# 3DP-GLCD.net
KiCad netlist of a schematic drawn in Altium Designer
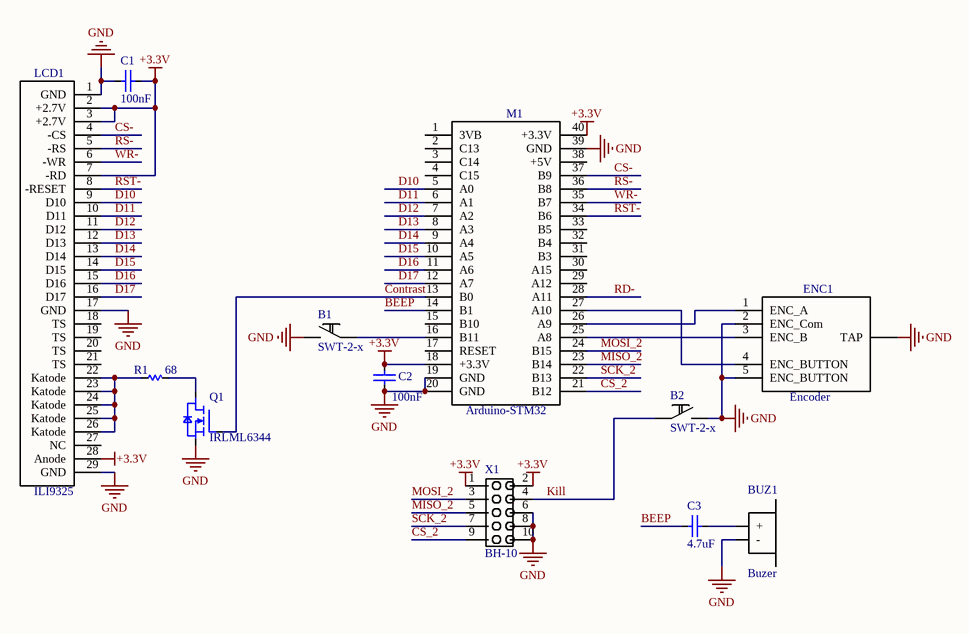
[diagram p0: 3DP-GLCD.SchDoc]

(export (version "E")
  (design (tool "Eeschema 10.0.6"))
  (components
    (comp (ref "B1") (value "SWT-2-x") (footprint "SWT-2-x") (libsource (lib "My_Schlib") (part "SWT-2-x")))
    (comp (ref "B2") (value "SWT-2-x") (footprint "SWT-2-x") (libsource (lib "My_Schlib") (part "SWT-2-x")))
    (comp (ref "BUZ1") (value "Buzer") (footprint "Buzer_12xx") (libsource (lib "My_Schlib") (part "Buzer")))
    (comp (ref "C1")
      (value "100nF")
      (footprint "C0805_Murata")
      (fields
        (field (name "PART NUMBER") "GRM21BR71H104KA01L")
        (field (name "VOLTAGE") "50V")
        (field (name "TOLERANCE") "10 %")
      )
      (libsource (lib "CorpLib") (part "Cap"))
    )
    (comp (ref "C2")
      (value "100nF")
      (footprint "C0805_Murata")
      (fields
        (field (name "PART NUMBER") "GRM21BR71H104KA01L")
        (field (name "VOLTAGE") "50V")
        (field (name "TOLERANCE") "10 %")
      )
      (libsource (lib "CorpLib") (part "Cap"))
    )
    (comp (ref "C3")
      (value "4.7uF")
      (footprint "C1206_Murata")
      (fields
        (field (name "PART NUMBER") "GRM31CR71H475KA12L")
        (field (name "VOLTAGE") "50V")
        (field (name "TOLERANCE") "10 %")
      )
      (libsource (lib "CorpLib") (part "Cap"))
    )
    (comp (ref "ENC1")
      (value "Encoder")
      (footprint "Encoder_bot")
      (description "Rotary Encoder with button")
      (libsource (lib "My_Schlib") (part "Encoder"))
    )
    (comp (ref "LCD1")
      (value "ILI9325")
      (footprint "LCD-ILI9325-29pin-top")
      (description "TFT LCD")
      (libsource (lib "My_Schlib") (part "LCD-ILI9325-29pin"))
    )
    (comp (ref "M1")
      (value "Arduino-STM32")
      (footprint "ARDUINO-STM32")
      (libsource (lib "My_Schlib") (part "ARDUINO-STM32"))
    )
    (comp (ref "Q1")
      (value "IRLML6344")
      (footprint "SOT23-3_IR")
      (description "30 V, 5.0 A, 0.029 Ohm Single N-Channel HEXFET Power MOSFET")
      (fields
        (field (name "PART NUMBER") "IRLML6344TRPBF")
        (field (name "PART LABEL") "IRLML6344")
        (field (name "MANUFACTURER") "International Rectifier")
      )
      (libsource (lib "CorpLib") (part "IRLML6344"))
    )
    (comp (ref "R1")
      (value "68")
      (footprint "R0805_UniOhm")
      (fields
        (field (name "PART NUMBER") "0805S8F4700T50")
        (field (name "TOLERANCE") "1 %")
        (field (name "MANUFACTURER") "uniOhm")
      )
      (libsource (lib "CorpLib") (part "R"))
    )
    (comp (ref "X1") (value "BH-10") (footprint "BH-10") (libsource (lib "My_Schlib") (part "BH-10_2")))
  )
  (nets
    (net (code "1") (name "+3.3V") (class "Default")
      (node (ref "C1") (pin "1") (pinfunction "1_1") (pintype "passive"))
      (node (ref "C2") (pin "1") (pinfunction "1_1") (pintype "passive"))
      (node (ref "LCD1") (pin "2") (pinfunction "+2.7V_2") (pintype "passive"))
      (node (ref "LCD1") (pin "28") (pinfunction "Anode_28") (pintype "passive"))
      (node (ref "LCD1") (pin "3") (pinfunction "+2.7V_3") (pintype "passive"))
      (node (ref "LCD1") (pin "7") (pinfunction "-RD_7") (pintype "passive"))
      (node (ref "M1") (pin "18") (pinfunction "+3.3V_18") (pintype "passive"))
      (node (ref "M1") (pin "40") (pinfunction "+3.3V_40") (pintype "passive"))
      (node (ref "X1") (pin "1") (pinfunction "1_1") (pintype "passive"))
      (node (ref "X1") (pin "2") (pinfunction "2_2") (pintype "passive"))
    )
    (net (code "2") (name "/BEEP") (class "Default")
      (node (ref "C3") (pin "1") (pinfunction "1_1") (pintype "passive"))
      (node (ref "M1") (pin "14") (pinfunction "B1_14") (pintype "passive"))
    )
    (net (code "3") (name "/CS-") (class "Default")
      (node (ref "LCD1") (pin "4") (pinfunction "-CS_4") (pintype "passive"))
      (node (ref "M1") (pin "37") (pinfunction "B9_37") (pintype "passive"))
    )
    (net (code "4") (name "/CS_2") (class "Default")
      (node (ref "M1") (pin "21") (pinfunction "B12_21") (pintype "passive"))
      (node (ref "X1") (pin "9") (pinfunction "9_9") (pintype "passive"))
    )
    (net (code "5") (name "/Contrast") (class "Default")
      (node (ref "M1") (pin "13") (pinfunction "B0_13") (pintype "passive"))
      (node (ref "Q1") (pin "1") (pinfunction "G_1") (pintype "passive"))
    )
    (net (code "6") (name "/D10") (class "Default")
      (node (ref "LCD1") (pin "9") (pinfunction "D10_9") (pintype "passive"))
      (node (ref "M1") (pin "5") (pinfunction "A0_5") (pintype "passive"))
    )
    (net (code "7") (name "/D11") (class "Default")
      (node (ref "LCD1") (pin "10") (pinfunction "D11_10") (pintype "passive"))
      (node (ref "M1") (pin "6") (pinfunction "A1_6") (pintype "passive"))
    )
    (net (code "8") (name "/D12") (class "Default")
      (node (ref "LCD1") (pin "11") (pinfunction "D12_11") (pintype "passive"))
      (node (ref "M1") (pin "7") (pinfunction "A2_7") (pintype "passive"))
    )
    (net (code "9") (name "/D13") (class "Default")
      (node (ref "LCD1") (pin "12") (pinfunction "D13_12") (pintype "passive"))
      (node (ref "M1") (pin "8") (pinfunction "A3_8") (pintype "passive"))
    )
    (net (code "10") (name "/D14") (class "Default")
      (node (ref "LCD1") (pin "13") (pinfunction "D14_13") (pintype "passive"))
      (node (ref "M1") (pin "9") (pinfunction "A4_9") (pintype "passive"))
    )
    (net (code "11") (name "/D15") (class "Default")
      (node (ref "LCD1") (pin "14") (pinfunction "D15_14") (pintype "passive"))
      (node (ref "M1") (pin "10") (pinfunction "A5_10") (pintype "passive"))
    )
    (net (code "12") (name "/D16") (class "Default")
      (node (ref "LCD1") (pin "15") (pinfunction "D16_15") (pintype "passive"))
      (node (ref "M1") (pin "11") (pinfunction "A6_11") (pintype "passive"))
    )
    (net (code "13") (name "/D17") (class "Default")
      (node (ref "LCD1") (pin "16") (pinfunction "D17_16") (pintype "passive"))
      (node (ref "M1") (pin "12") (pinfunction "A7_12") (pintype "passive"))
    )
    (net (code "14") (name "/Kill") (class "Default")
      (node (ref "B2") (pin "1") (pinfunction "1_1") (pintype "passive"))
      (node (ref "X1") (pin "4") (pinfunction "4_4") (pintype "passive"))
    )
    (net (code "15") (name "/MISO_2") (class "Default")
      (node (ref "M1") (pin "23") (pinfunction "B14_23") (pintype "passive"))
      (node (ref "X1") (pin "5") (pinfunction "5_5") (pintype "passive"))
    )
    (net (code "16") (name "/MOSI_2") (class "Default")
      (node (ref "M1") (pin "24") (pinfunction "B15_24") (pintype "passive"))
      (node (ref "X1") (pin "3") (pinfunction "3_3") (pintype "passive"))
    )
    (net (code "17") (name "/RD-") (class "Default")
      (node (ref "M1") (pin "28") (pinfunction "A11_28") (pintype "passive"))
    )
    (net (code "18") (name "/RS-") (class "Default")
      (node (ref "LCD1") (pin "5") (pinfunction "-RS_5") (pintype "passive"))
      (node (ref "M1") (pin "36") (pinfunction "B8_36") (pintype "passive"))
    )
    (net (code "19") (name "/RST-") (class "Default")
      (node (ref "LCD1") (pin "8") (pinfunction "-RESET_8") (pintype "passive"))
      (node (ref "M1") (pin "34") (pinfunction "B6_34") (pintype "passive"))
    )
    (net (code "20") (name "/SCK_2") (class "Default")
      (node (ref "M1") (pin "22") (pinfunction "B13_22") (pintype "passive"))
      (node (ref "X1") (pin "7") (pinfunction "7_7") (pintype "passive"))
    )
    (net (code "21") (name "/WR-") (class "Default")
      (node (ref "LCD1") (pin "6") (pinfunction "-WR_6") (pintype "passive"))
      (node (ref "M1") (pin "35") (pinfunction "B7_35") (pintype "passive"))
    )
    (net (code "22") (name "GND") (class "Default")
      (node (ref "B1") (pin "2") (pinfunction "2_2") (pintype "passive"))
      (node (ref "B2") (pin "2") (pinfunction "2_2") (pintype "passive"))
      (node (ref "BUZ1") (pin "2") (pinfunction "-_2") (pintype "passive"))
      (node (ref "C1") (pin "2") (pinfunction "2_2") (pintype "passive"))
      (node (ref "C2") (pin "2") (pinfunction "2_2") (pintype "passive"))
      (node (ref "ENC1") (pin "0") (pinfunction "TAP_0") (pintype "passive"))
      (node (ref "ENC1") (pin "2") (pinfunction "ENC_Com_2") (pintype "passive"))
      (node (ref "ENC1") (pin "5") (pinfunction "ENC_BUTTON_5") (pintype "passive"))
      (node (ref "LCD1") (pin "1") (pinfunction "GND_1") (pintype "passive"))
      (node (ref "LCD1") (pin "17") (pinfunction "GND_17") (pintype "passive"))
      (node (ref "LCD1") (pin "29") (pinfunction "GND_29") (pintype "passive"))
      (node (ref "M1") (pin "19") (pinfunction "GND_19") (pintype "passive"))
      (node (ref "M1") (pin "20") (pinfunction "GND_20") (pintype "passive"))
      (node (ref "M1") (pin "39") (pinfunction "GND_39") (pintype "passive"))
      (node (ref "Q1") (pin "2") (pinfunction "S_2") (pintype "passive"))
      (node (ref "X1") (pin "10") (pinfunction "10_10") (pintype "passive"))
      (node (ref "X1") (pin "6") (pinfunction "6_6") (pintype "passive"))
      (node (ref "X1") (pin "8") (pinfunction "8_8") (pintype "passive"))
    )
    (net (code "23") (name "Net-(BUZ1-+)") (class "Default")
      (node (ref "BUZ1") (pin "1") (pinfunction "+_1") (pintype "passive"))
      (node (ref "C3") (pin "2") (pinfunction "2_2") (pintype "passive"))
    )
    (net (code "24") (name "Net-(ENC1-ENC_A)") (class "Default")
      (node (ref "ENC1") (pin "1") (pinfunction "ENC_A_1") (pintype "passive"))
      (node (ref "M1") (pin "26") (pinfunction "A9_26") (pintype "passive"))
    )
    (net (code "25") (name "Net-(ENC1-ENC_B)") (class "Default")
      (node (ref "ENC1") (pin "3") (pinfunction "ENC_B_3") (pintype "passive"))
      (node (ref "M1") (pin "25") (pinfunction "A8_25") (pintype "passive"))
    )
    (net (code "26") (name "Net-(LCD1-Katode-Pad22)") (class "Default")
      (node (ref "LCD1") (pin "22") (pinfunction "Katode_22") (pintype "passive"))
      (node (ref "LCD1") (pin "23") (pinfunction "Katode_23") (pintype "passive"))
      (node (ref "LCD1") (pin "24") (pinfunction "Katode_24") (pintype "passive"))
      (node (ref "LCD1") (pin "25") (pinfunction "Katode_25") (pintype "passive"))
      (node (ref "LCD1") (pin "26") (pinfunction "Katode_26") (pintype "passive"))
      (node (ref "R1") (pin "1") (pinfunction "1_1") (pintype "passive"))
    )
    (net (code "27") (name "Net-(M1-A10)") (class "Default")
      (node (ref "ENC1") (pin "4") (pinfunction "ENC_BUTTON_4") (pintype "passive"))
      (node (ref "M1") (pin "27") (pinfunction "A10_27") (pintype "passive"))
    )
    (net (code "28") (name "Net-(M1-B11)") (class "Default")
      (node (ref "B1") (pin "1") (pinfunction "1_1") (pintype "passive"))
      (node (ref "M1") (pin "16") (pinfunction "B11_16") (pintype "passive"))
    )
    (net (code "29") (name "Net-(Q1-D)") (class "Default")
      (node (ref "Q1") (pin "3") (pinfunction "D_3") (pintype "passive"))
      (node (ref "R1") (pin "2") (pinfunction "2_2") (pintype "passive"))
    )
    (net (code "30") (name "unconnected-(LCD1-NC-Pad27)") (class "Default")
      (node (ref "LCD1") (pin "27") (pinfunction "NC_27") (pintype "passive"))
    )
    (net (code "31") (name "unconnected-(LCD1-TS-Pad18)") (class "Default")
      (node (ref "LCD1") (pin "18") (pinfunction "TS_18") (pintype "passive"))
    )
    (net (code "32") (name "unconnected-(LCD1-TS-Pad19)") (class "Default")
      (node (ref "LCD1") (pin "19") (pinfunction "TS_19") (pintype "passive"))
    )
    (net (code "33") (name "unconnected-(LCD1-TS-Pad20)") (class "Default")
      (node (ref "LCD1") (pin "20") (pinfunction "TS_20") (pintype "passive"))
    )
    (net (code "34") (name "unconnected-(LCD1-TS-Pad21)") (class "Default")
      (node (ref "LCD1") (pin "21") (pinfunction "TS_21") (pintype "passive"))
    )
    (net (code "35") (name "unconnected-(M1-+5V-Pad38)") (class "Default")
      (node (ref "M1") (pin "38") (pinfunction "+5V_38") (pintype "passive"))
    )
    (net (code "36") (name "unconnected-(M1-3VB-Pad1)") (class "Default")
      (node (ref "M1") (pin "1") (pinfunction "3VB_1") (pintype "passive"))
    )
    (net (code "37") (name "unconnected-(M1-A12-Pad29)") (class "Default")
      (node (ref "M1") (pin "29") (pinfunction "A12_29") (pintype "passive"))
    )
    (net (code "38") (name "unconnected-(M1-A15-Pad30)") (class "Default")
      (node (ref "M1") (pin "30") (pinfunction "A15_30") (pintype "passive"))
    )
    (net (code "39") (name "unconnected-(M1-B3-Pad31)") (class "Default")
      (node (ref "M1") (pin "31") (pinfunction "B3_31") (pintype "passive"))
    )
    (net (code "40") (name "unconnected-(M1-B4-Pad32)") (class "Default")
      (node (ref "M1") (pin "32") (pinfunction "B4_32") (pintype "passive"))
    )
    (net (code "41") (name "unconnected-(M1-B5-Pad33)") (class "Default")
      (node (ref "M1") (pin "33") (pinfunction "B5_33") (pintype "passive"))
    )
    (net (code "42") (name "unconnected-(M1-B10-Pad15)") (class "Default")
      (node (ref "M1") (pin "15") (pinfunction "B10_15") (pintype "passive"))
    )
    (net (code "43") (name "unconnected-(M1-C13-Pad2)") (class "Default")
      (node (ref "M1") (pin "2") (pinfunction "C13_2") (pintype "passive"))
    )
    (net (code "44") (name "unconnected-(M1-C14-Pad3)") (class "Default")
      (node (ref "M1") (pin "3") (pinfunction "C14_3") (pintype "passive"))
    )
    (net (code "45") (name "unconnected-(M1-C15-Pad4)") (class "Default")
      (node (ref "M1") (pin "4") (pinfunction "C15_4") (pintype "passive"))
    )
    (net (code "46") (name "unconnected-(M1-RESET-Pad17)") (class "Default")
      (node (ref "M1") (pin "17") (pinfunction "RESET_17") (pintype "passive"))
    )
  )
)
